# 1A19J3_1A21J3_A.net
KiCad netlist of a schematic drawn in Altium Designer
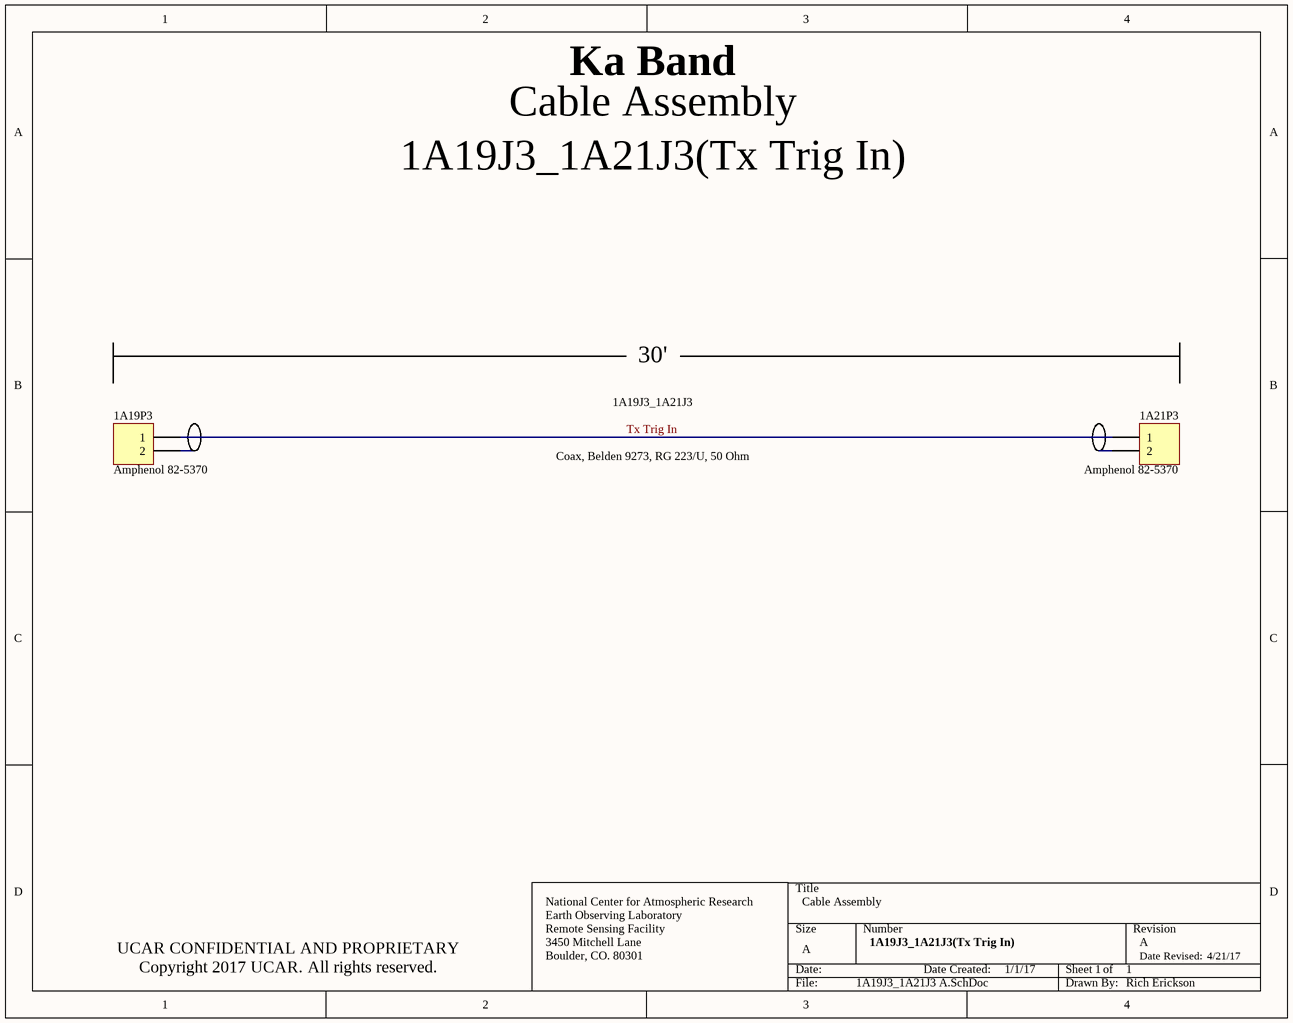
[diagram p0: 1A19J3_1A21J3 A.SchDoc]

(export (version "E")
  (design (tool "Eeschema 10.0.6"))
  (components
    (comp (ref "1A19P3")
      (value "Amphenol 82-5370")
      (footprint "HDR1X2")
      (description "Header, 2-Pin")
      (fields (field (name "PUBLISHER") "Altium Limited"))
      (libsource (lib "") (part "Header 2_1"))
    )
    (comp (ref "1A21P3")
      (value "Amphenol 82-5370")
      (footprint "HDR1X2")
      (description "Header, 2-Pin")
      (fields (field (name "PUBLISHER") "Altium Limited"))
      (libsource (lib "Miscellaneous Connectors") (part "Header 2"))
    )
  )
  (nets
    (net (code "1") (name "/Tx Trig In") (class "Default")
      (node (ref "1A19P3") (pin "1") (pinfunction "1_1") (pintype "passive"))
      (node (ref "1A21P3") (pin "1") (pinfunction "1_1") (pintype "passive"))
    )
    (net (code "2") (name "unconnected-(1A19P3-Pad2)") (class "Default")
      (node (ref "1A19P3") (pin "2") (pinfunction "2_2") (pintype "passive"))
    )
    (net (code "3") (name "unconnected-(1A21P3-Pad2)") (class "Default")
      (node (ref "1A21P3") (pin "2") (pinfunction "2_2") (pintype "passive"))
    )
  )
)
